# opendeep_dbg001_cnc_v01.net
KiCad netlist of a schematic drawn in EasyEDA Pro
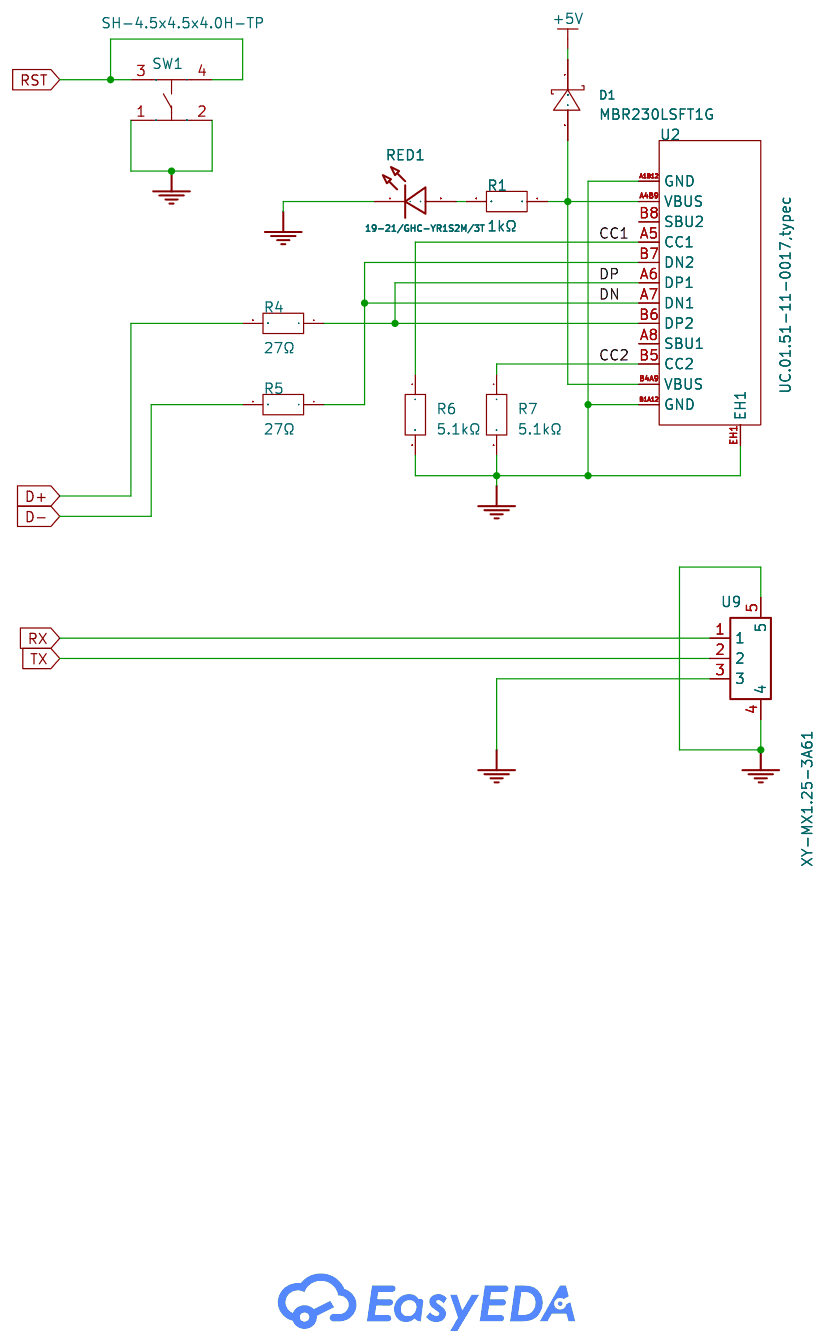
[diagram p0: schematic sheet]

(export (version "E")
  (design (tool "Eeschema 10.0.6"))
  (components
    (comp (ref "D1")
      (value "MBR230LSFT1G")
      (footprint "easyedapro:SOD-123FL_L2.7-W1.8-LS3.8-RD")
      (fields (field (name "Manufacturer") "onsemi(安森美)"))
      (libsource (lib "easyedapro") (part "MBR230LSFT1G"))
    )
    (comp (ref "R1")
      (value "1kΩ")
      (footprint "easyedapro:R0603")
      (fields (field (name "Manufacturer Part") "RCC06031K50FKEA") (field (name "Manufacturer") "VISHAY(威世)"))
      (libsource (lib "easyedapro") (part "RCC06031K50FKEA"))
    )
    (comp (ref "R4")
      (value "27Ω")
      (footprint "easyedapro:R0603")
      (fields (field (name "Manufacturer Part") "RCC06031K50FKEA") (field (name "Manufacturer") "VISHAY(威世)"))
      (libsource (lib "easyedapro") (part "RCC06031K50FKEA"))
    )
    (comp (ref "R5")
      (value "27Ω")
      (footprint "easyedapro:R0603")
      (fields (field (name "Manufacturer Part") "RCC06031K50FKEA") (field (name "Manufacturer") "VISHAY(威世)"))
      (libsource (lib "easyedapro") (part "RCC06031K50FKEA"))
    )
    (comp (ref "R6")
      (value "5.1kΩ")
      (footprint "easyedapro:R0603")
      (fields (field (name "Manufacturer Part") "RCC06031K50FKEA") (field (name "Manufacturer") "VISHAY(威世)"))
      (libsource (lib "easyedapro") (part "RCC06031K50FKEA"))
    )
    (comp (ref "R7")
      (value "5.1kΩ")
      (footprint "easyedapro:R0603")
      (fields (field (name "Manufacturer Part") "RCC06031K50FKEA") (field (name "Manufacturer") "VISHAY(威世)"))
      (libsource (lib "easyedapro") (part "RCC06031K50FKEA"))
    )
    (comp (ref "RED1")
      (value "19-21/GHC-YR1S2M/3T")
      (footprint "easyedapro:LED-SMD_L1.6-W0.8-RD")
      (fields (field (name "Manufacturer") "EVERLIGHT(亿光)") (field (name "Contributor") "LCSC"))
      (libsource (lib "easyedapro") (part "19-21/GHC-YR1S2M/3T"))
    )
    (comp (ref "SW1")
      (value "SH-4.5x4.5x4.0H-TP")
      (footprint "easyedapro:SW-SMD_4P-SH-4.5X4.5X4.0H-TP")
      (fields (field (name "Manufacturer") "SHOU HAN(首韩)"))
      (libsource (lib "easyedapro") (part "SH-4.5X4.5X4.0H-TP"))
    )
    (comp (ref "U2")
      (value "UC.01.51-11-0017,typec")
      (footprint "easyedapro:TYPE-C-SMD_UC.01.51-11-0017")
      (libsource (lib "easyedapro") (part "UC.01.51-11-0017,TYPEC"))
    )
    (comp (ref "U9")
      (value "XY-MX1.25-3A61")
      (footprint "easyedapro:CONN-SMD_3P-P1.25_XY-MX1.25-3A61")
      (fields (field (name "Manufacturer") "XYECONN(辛译)") (field (name "Contributor") "lcsc"))
      (libsource (lib "easyedapro") (part "XY-MX1.25-3A61"))
    )
  )
  (nets
    (net (code "1") (name "+5V") (class "Default")
      (node (ref "D1") (pin "1") (pinfunction "C_1") (pintype "input"))
    )
    (net (code "2") (name "/CC1") (class "Default")
      (node (ref "R6") (pin "1") (pinfunction "1_1") (pintype "unspecified"))
      (node (ref "U2") (pin "A5") (pinfunction "CC1_A5") (pintype "unspecified"))
    )
    (net (code "3") (name "/CC2") (class "Default")
      (node (ref "R7") (pin "1") (pinfunction "1_1") (pintype "unspecified"))
      (node (ref "U2") (pin "B5") (pinfunction "CC2_B5") (pintype "unspecified"))
    )
    (net (code "4") (name "/DN") (class "Default")
      (node (ref "R5") (pin "1") (pinfunction "1_1") (pintype "unspecified"))
      (node (ref "U2") (pin "A7") (pinfunction "DN1_A7") (pintype "unspecified"))
      (node (ref "U2") (pin "B7") (pinfunction "DN2_B7") (pintype "unspecified"))
    )
    (net (code "5") (name "/DP") (class "Default")
      (node (ref "R4") (pin "1") (pinfunction "1_1") (pintype "unspecified"))
      (node (ref "U2") (pin "A6") (pinfunction "DP1_A6") (pintype "unspecified"))
      (node (ref "U2") (pin "B6") (pinfunction "DP2_B6") (pintype "unspecified"))
    )
    (net (code "6") (name "D+") (class "Default")
      (node (ref "R4") (pin "2") (pinfunction "2_2") (pintype "unspecified"))
    )
    (net (code "7") (name "D-") (class "Default")
      (node (ref "R5") (pin "2") (pinfunction "2_2") (pintype "unspecified"))
    )
    (net (code "8") (name "GND") (class "Default")
      (node (ref "R6") (pin "2") (pinfunction "2_2") (pintype "unspecified"))
      (node (ref "R7") (pin "2") (pinfunction "2_2") (pintype "unspecified"))
      (node (ref "RED1") (pin "1") (pinfunction "-_1") (pintype "unspecified"))
      (node (ref "SW1") (pin "1") (pinfunction "1_1") (pintype "unspecified"))
      (node (ref "SW1") (pin "2") (pinfunction "2_2") (pintype "unspecified"))
      (node (ref "U2") (pin "A1B12") (pinfunction "GND_A1B12") (pintype "unspecified"))
      (node (ref "U2") (pin "B1A12") (pinfunction "GND_B1A12") (pintype "unspecified"))
      (node (ref "U2") (pin "EH1") (pinfunction "EH1_EH1") (pintype "unspecified"))
      (node (ref "U9") (pin "3") (pinfunction "3_3") (pintype "unspecified"))
      (node (ref "U9") (pin "4") (pinfunction "4_4") (pintype "unspecified"))
      (node (ref "U9") (pin "5") (pinfunction "5_5") (pintype "unspecified"))
    )
    (net (code "9") (name "Net-(D1-A)") (class "Default")
      (node (ref "D1") (pin "2") (pinfunction "A_2") (pintype "input"))
      (node (ref "R1") (pin "1") (pinfunction "1_1") (pintype "unspecified"))
      (node (ref "U2") (pin "A4B9") (pinfunction "VBUS_A4B9") (pintype "unspecified"))
      (node (ref "U2") (pin "B4A9") (pinfunction "VBUS_B4A9") (pintype "unspecified"))
    )
    (net (code "10") (name "Net-(RED1-+)") (class "Default")
      (node (ref "R1") (pin "2") (pinfunction "2_2") (pintype "unspecified"))
      (node (ref "RED1") (pin "2") (pinfunction "+_2") (pintype "unspecified"))
    )
    (net (code "11") (name "RST") (class "Default")
      (node (ref "SW1") (pin "3") (pinfunction "3_3") (pintype "unspecified"))
      (node (ref "SW1") (pin "4") (pinfunction "4_4") (pintype "unspecified"))
    )
    (net (code "12") (name "RX") (class "Default")
      (node (ref "U9") (pin "1") (pinfunction "1_1") (pintype "unspecified"))
    )
    (net (code "13") (name "TX") (class "Default")
      (node (ref "U9") (pin "2") (pinfunction "2_2") (pintype "unspecified"))
    )
    (net (code "14") (name "unconnected-(U2-SBU1-PadA8)") (class "Default")
      (node (ref "U2") (pin "A8") (pinfunction "SBU1_A8") (pintype "unspecified"))
    )
    (net (code "15") (name "unconnected-(U2-SBU2-PadB8)") (class "Default")
      (node (ref "U2") (pin "B8") (pinfunction "SBU2_B8") (pintype "unspecified"))
    )
  )
)
